# T12.net
KiCad netlist of a schematic drawn in Altium Designer
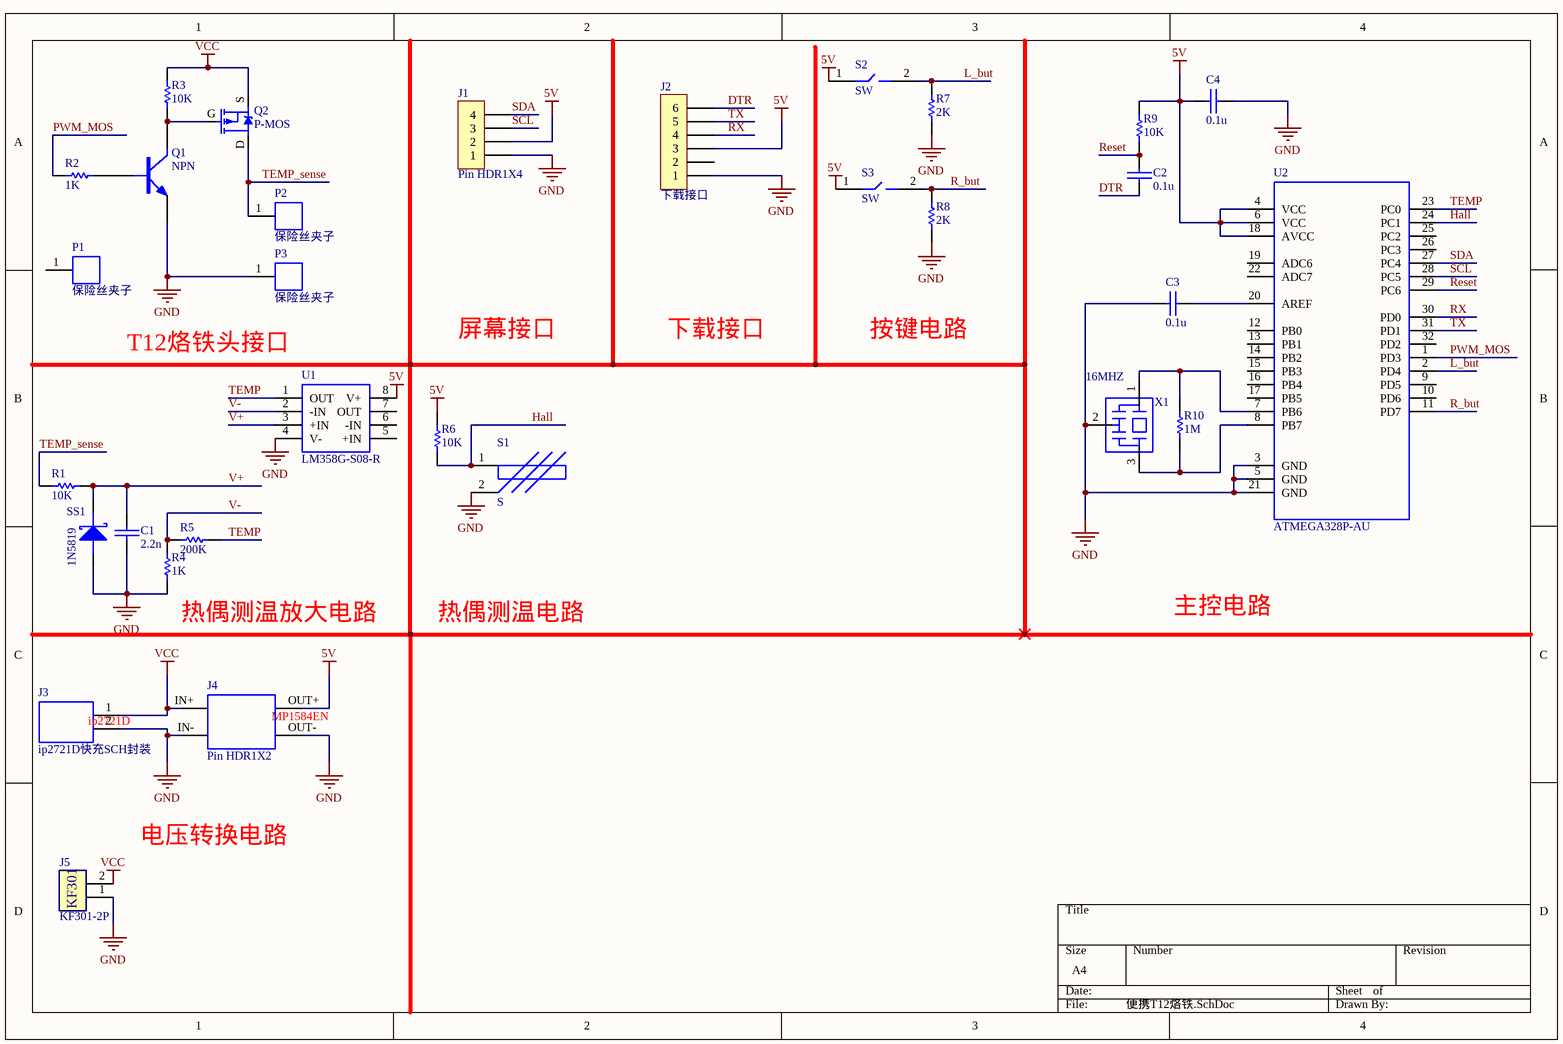
[diagram p0: 便携T12烙铁.SchDoc]

(export (version "E")
  (design (tool "Eeschema 10.0.6"))
  (components
    (comp (ref "C1")
      (value "2.2n")
      (footprint "0603C")
      (description "无极性电容")
      (libsource (lib "便携T12烙铁") (part "CAP"))
    )
    (comp (ref "C2")
      (value "0.1u")
      (footprint "0603C")
      (description "无极性电容")
      (libsource (lib "便携T12烙铁") (part "CAP"))
    )
    (comp (ref "C3")
      (value "0.1u")
      (footprint "0603C")
      (description "无极性电容")
      (libsource (lib "便携T12烙铁") (part "CAP"))
    )
    (comp (ref "C4")
      (value "0.1u")
      (footprint "0603C")
      (description "无极性电容")
      (libsource (lib "便携T12烙铁") (part "CAP"))
    )
    (comp (ref "J1")
      (value "Pin HDR1X4")
      (footprint "Pin HDR1X4/2.54mm-S")
      (description "0.91 i2c oled")
      (libsource (lib "便携T12烙铁") (part "Pin HDR1X4"))
    )
    (comp (ref "J2")
      (value "下载接口")
      (footprint "Pin HDR1X6/2.54mm-S")
      (libsource (lib "便携T12烙铁") (part "Pin HDR1X6"))
    )
    (comp (ref "J3")
      (value "ip2721D快充SCH封装")
      (footprint "ip2721D快充PCB封装")
      (libsource (lib "便携T12烙铁") (part "ip2721D快充SCH封装"))
    )
    (comp (ref "J4")
      (value "Pin HDR1X2")
      (footprint "MP1584EN稳压PCB封装")
      (libsource (lib "便携T12烙铁") (part "MP1584EN稳压SCH封装"))
    )
    (comp (ref "J5")
      (value "KF301-2P")
      (footprint "KF301-5.0-2P")
      (libsource (lib "便携T12烙铁") (part "KF301-2P"))
    )
    (comp (ref "P1")
      (value "保险丝夹子")
      (footprint "FUSE-5x20")
      (description "保险丝夹子\r\n5X20")
      (libsource (lib "便携T12烙铁") (part "保险丝夹子"))
    )
    (comp (ref "P2")
      (value "保险丝夹子")
      (footprint "FUSE-5x20")
      (description "保险丝夹子\r\n5X20")
      (libsource (lib "便携T12烙铁") (part "保险丝夹子"))
    )
    (comp (ref "P3")
      (value "保险丝夹子")
      (footprint "FUSE-5x20")
      (description "保险丝夹子\r\n5X20")
      (libsource (lib "便携T12烙铁") (part "保险丝夹子"))
    )
    (comp (ref "Q1")
      (value "NPN")
      (footprint "SOT-23")
      (description "NPN三极管\r\n2SC3356-T1B-A")
      (libsource (lib "便携T12烙铁") (part "NPN"))
    )
    (comp (ref "Q2")
      (value "P-MOS")
      (footprint "TO263-3B")
      (description "P沟道场效应管\r\nIRF4905STRLPBF")
      (libsource (lib "便携T12烙铁") (part "P-MOS"))
    )
    (comp (ref "R1")
      (value "10K")
      (footprint "0603R")
      (description "电阻")
      (libsource (lib "便携T12烙铁") (part "RES"))
    )
    (comp (ref "R2")
      (value "1K")
      (footprint "0603R")
      (description "电阻")
      (libsource (lib "便携T12烙铁") (part "RES"))
    )
    (comp (ref "R3")
      (value "10K")
      (footprint "0805R")
      (description "电阻")
      (libsource (lib "便携T12烙铁") (part "RES"))
    )
    (comp (ref "R4")
      (value "1K")
      (footprint "0603R")
      (description "电阻")
      (libsource (lib "便携T12烙铁") (part "RES"))
    )
    (comp (ref "R5")
      (value "200K")
      (footprint "0603R")
      (description "电阻")
      (libsource (lib "便携T12烙铁") (part "RES"))
    )
    (comp (ref "R6")
      (value "10K")
      (footprint "0603R")
      (description "电阻")
      (libsource (lib "便携T12烙铁") (part "RES"))
    )
    (comp (ref "R7")
      (value "2K")
      (footprint "0603R")
      (description "电阻")
      (libsource (lib "便携T12烙铁") (part "RES"))
    )
    (comp (ref "R8")
      (value "2K")
      (footprint "0603R")
      (description "电阻")
      (libsource (lib "便携T12烙铁") (part "RES"))
    )
    (comp (ref "R9")
      (value "10K")
      (footprint "0603R")
      (description "电阻")
      (libsource (lib "便携T12烙铁") (part "RES"))
    )
    (comp (ref "R10")
      (value "1M")
      (footprint "0603R")
      (description "电阻")
      (libsource (lib "便携T12烙铁") (part "RES"))
    )
    (comp (ref "S1")
      (value "S")
      (footprint "S")
      (description "震动开关\r\nSW180  建议SW18015")
      (libsource (lib "便携T12烙铁") (part "S"))
    )
    (comp (ref "S2")
      (value "SW")
      (footprint "TSW 3*6*4.3-S-W")
      (description "侧立按键开关\r\n3*6*4.3")
      (libsource (lib "便携T12烙铁") (part "SW"))
    )
    (comp (ref "S3")
      (value "SW")
      (footprint "TSW 3*6*4.3-S-W")
      (description "侧立按键开关\r\n3*6*4.3")
      (libsource (lib "便携T12烙铁") (part "SW"))
    )
    (comp (ref "SS1")
      (value "1N5819")
      (footprint "SMA/DO-214AC")
      (description "肖特基二极管SS12")
      (libsource (lib "便携T12烙铁") (part "DIODE SCHOTTKY"))
    )
    (comp (ref "U1")
      (value "LM358G-S08-R")
      (footprint "SOP8")
      (description "运放")
      (libsource (lib "便携T12烙铁") (part "LM358G-S08-R"))
    )
    (comp (ref "U2")
      (value "ATMEGA328P-AU")
      (footprint "TQFP32 7x7_M")
      (libsource (lib "便携T12烙铁") (part "ATMEGA328P-AU"))
    )
    (comp (ref "X1")
      (value "16MHZ")
      (footprint "晶振3213")
      (description "晶振3213")
      (libsource (lib "便携T12烙铁") (part "晶振3213"))
    )
  )
  (nets
    (net (code "1") (name "/DTR") (class "Default")
      (node (ref "C2") (pin "1") (pinfunction "1_1") (pintype "passive"))
      (node (ref "J2") (pin "6") (pinfunction "6_6") (pintype "passive"))
    )
    (net (code "2") (name "/Hall") (class "Default")
      (node (ref "R6") (pin "1") (pinfunction "1_1") (pintype "passive"))
      (node (ref "S1") (pin "1") (pinfunction "1_1") (pintype "passive"))
      (node (ref "U2") (pin "24") (pinfunction "PC1_24") (pintype "passive"))
    )
    (net (code "3") (name "/L_but") (class "Default")
      (node (ref "R7") (pin "2") (pinfunction "2_2") (pintype "passive"))
      (node (ref "S2") (pin "2") (pinfunction "2_2") (pintype "passive"))
      (node (ref "U2") (pin "2") (pinfunction "PD4_2") (pintype "passive"))
    )
    (net (code "4") (name "/PWM_MOS") (class "Default")
      (node (ref "R2") (pin "2") (pinfunction "2_2") (pintype "passive"))
      (node (ref "U2") (pin "1") (pinfunction "PD3_1") (pintype "passive"))
    )
    (net (code "5") (name "/RX") (class "Default")
      (node (ref "J2") (pin "4") (pinfunction "4_4") (pintype "passive"))
      (node (ref "U2") (pin "30") (pinfunction "PD0_30") (pintype "passive"))
    )
    (net (code "6") (name "/R_but") (class "Default")
      (node (ref "R8") (pin "2") (pinfunction "2_2") (pintype "passive"))
      (node (ref "S3") (pin "2") (pinfunction "2_2") (pintype "passive"))
      (node (ref "U2") (pin "11") (pinfunction "PD7_11") (pintype "passive"))
    )
    (net (code "7") (name "/Reset") (class "Default")
      (node (ref "C2") (pin "2") (pinfunction "2_2") (pintype "passive"))
      (node (ref "R9") (pin "1") (pinfunction "1_1") (pintype "passive"))
      (node (ref "U2") (pin "29") (pinfunction "PC6_29") (pintype "passive"))
    )
    (net (code "8") (name "/SCL") (class "Default")
      (node (ref "J1") (pin "3") (pinfunction "3_3") (pintype "passive"))
      (node (ref "U2") (pin "28") (pinfunction "PC5_28") (pintype "passive"))
    )
    (net (code "9") (name "/SDA") (class "Default")
      (node (ref "J1") (pin "4") (pinfunction "4_4") (pintype "passive"))
      (node (ref "U2") (pin "27") (pinfunction "PC4_27") (pintype "passive"))
    )
    (net (code "10") (name "/TEMP") (class "Default")
      (node (ref "R5") (pin "1") (pinfunction "1_1") (pintype "passive"))
      (node (ref "U1") (pin "1") (pinfunction "OUT_1") (pintype "passive"))
      (node (ref "U2") (pin "23") (pinfunction "PC0_23") (pintype "passive"))
    )
    (net (code "11") (name "/TEMP_sense") (class "Default")
      (node (ref "P2") (pin "1") (pinfunction "1_1") (pintype "passive"))
      (node (ref "Q2") (pin "D") (pinfunction "D_D") (pintype "passive"))
      (node (ref "R1") (pin "1") (pinfunction "1_1") (pintype "passive"))
    )
    (net (code "12") (name "/TX") (class "Default")
      (node (ref "J2") (pin "5") (pinfunction "5_5") (pintype "passive"))
      (node (ref "U2") (pin "31") (pinfunction "PD1_31") (pintype "passive"))
    )
    (net (code "13") (name "/V+") (class "Default")
      (node (ref "C1") (pin "2") (pinfunction "2_2") (pintype "passive"))
      (node (ref "R1") (pin "2") (pinfunction "2_2") (pintype "passive"))
      (node (ref "SS1") (pin "K") (pinfunction "K_K") (pintype "passive"))
      (node (ref "U1") (pin "3") (pinfunction "+IN_3") (pintype "passive"))
    )
    (net (code "14") (name "/V-") (class "Default")
      (node (ref "R4") (pin "1") (pinfunction "1_1") (pintype "passive"))
      (node (ref "R5") (pin "2") (pinfunction "2_2") (pintype "passive"))
      (node (ref "U1") (pin "2") (pinfunction "-IN_2") (pintype "passive"))
    )
    (net (code "15") (name "5V") (class "Default")
      (node (ref "C4") (pin "1") (pinfunction "1_1") (pintype "passive"))
      (node (ref "J1") (pin "2") (pinfunction "2_2") (pintype "passive"))
      (node (ref "J2") (pin "3") (pinfunction "3_3") (pintype "passive"))
      (node (ref "J4") (pin "OUT+") (pinfunction "OUT+_OUT+") (pintype "passive"))
      (node (ref "R6") (pin "2") (pinfunction "2_2") (pintype "passive"))
      (node (ref "R9") (pin "2") (pinfunction "2_2") (pintype "passive"))
      (node (ref "S2") (pin "1") (pinfunction "A1_1") (pintype "passive"))
      (node (ref "S3") (pin "1") (pinfunction "A1_1") (pintype "passive"))
      (node (ref "U1") (pin "8") (pinfunction "V+_8") (pintype "passive"))
      (node (ref "U2") (pin "18") (pinfunction "AVCC_18") (pintype "passive"))
      (node (ref "U2") (pin "4") (pinfunction "VCC_4") (pintype "passive"))
      (node (ref "U2") (pin "6") (pinfunction "VCC_6") (pintype "passive"))
    )
    (net (code "16") (name "GND") (class "Default")
      (node (ref "C1") (pin "1") (pinfunction "1_1") (pintype "passive"))
      (node (ref "C3") (pin "2") (pinfunction "2_2") (pintype "passive"))
      (node (ref "C4") (pin "2") (pinfunction "2_2") (pintype "passive"))
      (node (ref "J1") (pin "1") (pinfunction "1_1") (pintype "passive"))
      (node (ref "J2") (pin "1") (pinfunction "1_1") (pintype "passive"))
      (node (ref "J3") (pin "2") (pinfunction "-_2") (pintype "passive"))
      (node (ref "J4") (pin "IN-") (pinfunction "IN-_IN-") (pintype "passive"))
      (node (ref "J4") (pin "OUT-") (pinfunction "OUT-_OUT-") (pintype "passive"))
      (node (ref "J5") (pin "1") (pinfunction "1_1") (pintype "passive"))
      (node (ref "P3") (pin "1") (pinfunction "1_1") (pintype "passive"))
      (node (ref "Q1") (pin "E") (pinfunction "E_E") (pintype "passive"))
      (node (ref "R4") (pin "2") (pinfunction "2_2") (pintype "passive"))
      (node (ref "R7") (pin "1") (pinfunction "1_1") (pintype "passive"))
      (node (ref "R8") (pin "1") (pinfunction "1_1") (pintype "passive"))
      (node (ref "S1") (pin "2") (pinfunction "2_2") (pintype "passive"))
      (node (ref "SS1") (pin "A") (pinfunction "A_A") (pintype "passive"))
      (node (ref "U1") (pin "4") (pinfunction "V-_4") (pintype "passive"))
      (node (ref "U2") (pin "21") (pinfunction "GND_21") (pintype "passive"))
      (node (ref "U2") (pin "3") (pinfunction "GND_3") (pintype "passive"))
      (node (ref "U2") (pin "5") (pinfunction "GND_5") (pintype "passive"))
      (node (ref "X1") (pin "2") (pinfunction "2_2") (pintype "passive"))
    )
    (net (code "17") (name "Net-(Q1-PadB)") (class "Default")
      (node (ref "Q1") (pin "B") (pinfunction "B_B") (pintype "passive"))
      (node (ref "R2") (pin "1") (pinfunction "1_1") (pintype "passive"))
    )
    (net (code "18") (name "Net-(Q1-PadC)") (class "Default")
      (node (ref "Q1") (pin "C") (pinfunction "C_C") (pintype "passive"))
      (node (ref "Q2") (pin "G") (pinfunction "G_G") (pintype "passive"))
      (node (ref "R3") (pin "1") (pinfunction "1_1") (pintype "passive"))
    )
    (net (code "19") (name "Net-(U2-AREF)") (class "Default")
      (node (ref "C3") (pin "1") (pinfunction "1_1") (pintype "passive"))
      (node (ref "U2") (pin "20") (pinfunction "AREF_20") (pintype "passive"))
    )
    (net (code "20") (name "Net-(U2-PB6)") (class "Default")
      (node (ref "R10") (pin "2") (pinfunction "2_2") (pintype "passive"))
      (node (ref "U2") (pin "7") (pinfunction "PB6_7") (pintype "passive"))
      (node (ref "X1") (pin "1") (pinfunction "1_1") (pintype "passive"))
    )
    (net (code "21") (name "Net-(U2-PB7)") (class "Default")
      (node (ref "R10") (pin "1") (pinfunction "1_1") (pintype "passive"))
      (node (ref "U2") (pin "8") (pinfunction "PB7_8") (pintype "passive"))
      (node (ref "X1") (pin "3") (pinfunction "3_3") (pintype "passive"))
    )
    (net (code "22") (name "VCC") (class "Default")
      (node (ref "J3") (pin "1") (pinfunction "+_1") (pintype "passive"))
      (node (ref "J4") (pin "IN+") (pinfunction "IN+_IN+") (pintype "passive"))
      (node (ref "J5") (pin "2") (pinfunction "2_2") (pintype "passive"))
      (node (ref "Q2") (pin "S") (pinfunction "S_S") (pintype "passive"))
      (node (ref "R3") (pin "2") (pinfunction "2_2") (pintype "passive"))
    )
    (net (code "23") (name "unconnected-(J2-Pad2)") (class "Default")
      (node (ref "J2") (pin "2") (pinfunction "2_2") (pintype "passive"))
    )
    (net (code "24") (name "unconnected-(P1-Pad1)") (class "Default")
      (node (ref "P1") (pin "1") (pinfunction "1_1") (pintype "passive"))
    )
    (net (code "25") (name "unconnected-(U1-+IN-Pad5)") (class "Default")
      (node (ref "U1") (pin "5") (pinfunction "+IN_5") (pintype "passive"))
    )
    (net (code "26") (name "unconnected-(U1--IN-Pad6)") (class "Default")
      (node (ref "U1") (pin "6") (pinfunction "-IN_6") (pintype "passive"))
    )
    (net (code "27") (name "unconnected-(U1-OUT-Pad7)") (class "Default")
      (node (ref "U1") (pin "7") (pinfunction "OUT_7") (pintype "passive"))
    )
    (net (code "28") (name "unconnected-(U2-ADC6-Pad19)") (class "Default")
      (node (ref "U2") (pin "19") (pinfunction "ADC6_19") (pintype "passive"))
    )
    (net (code "29") (name "unconnected-(U2-ADC7-Pad22)") (class "Default")
      (node (ref "U2") (pin "22") (pinfunction "ADC7_22") (pintype "passive"))
    )
    (net (code "30") (name "unconnected-(U2-PB0-Pad12)") (class "Default")
      (node (ref "U2") (pin "12") (pinfunction "PB0_12") (pintype "passive"))
    )
    (net (code "31") (name "unconnected-(U2-PB1-Pad13)") (class "Default")
      (node (ref "U2") (pin "13") (pinfunction "PB1_13") (pintype "passive"))
    )
    (net (code "32") (name "unconnected-(U2-PB2-Pad14)") (class "Default")
      (node (ref "U2") (pin "14") (pinfunction "PB2_14") (pintype "passive"))
    )
    (net (code "33") (name "unconnected-(U2-PB3-Pad15)") (class "Default")
      (node (ref "U2") (pin "15") (pinfunction "PB3_15") (pintype "passive"))
    )
    (net (code "34") (name "unconnected-(U2-PB4-Pad16)") (class "Default")
      (node (ref "U2") (pin "16") (pinfunction "PB4_16") (pintype "passive"))
    )
    (net (code "35") (name "unconnected-(U2-PB5-Pad17)") (class "Default")
      (node (ref "U2") (pin "17") (pinfunction "PB5_17") (pintype "passive"))
    )
    (net (code "36") (name "unconnected-(U2-PC2-Pad25)") (class "Default")
      (node (ref "U2") (pin "25") (pinfunction "PC2_25") (pintype "passive"))
    )
    (net (code "37") (name "unconnected-(U2-PC3-Pad26)") (class "Default")
      (node (ref "U2") (pin "26") (pinfunction "PC3_26") (pintype "passive"))
    )
    (net (code "38") (name "unconnected-(U2-PD2-Pad32)") (class "Default")
      (node (ref "U2") (pin "32") (pinfunction "PD2_32") (pintype "passive"))
    )
    (net (code "39") (name "unconnected-(U2-PD5-Pad9)") (class "Default")
      (node (ref "U2") (pin "9") (pinfunction "PD5_9") (pintype "passive"))
    )
    (net (code "40") (name "unconnected-(U2-PD6-Pad10)") (class "Default")
      (node (ref "U2") (pin "10") (pinfunction "PD6_10") (pintype "passive"))
    )
  )
)
